# LDA_Board.net
KiCad netlist of a schematic drawn in EAGLE
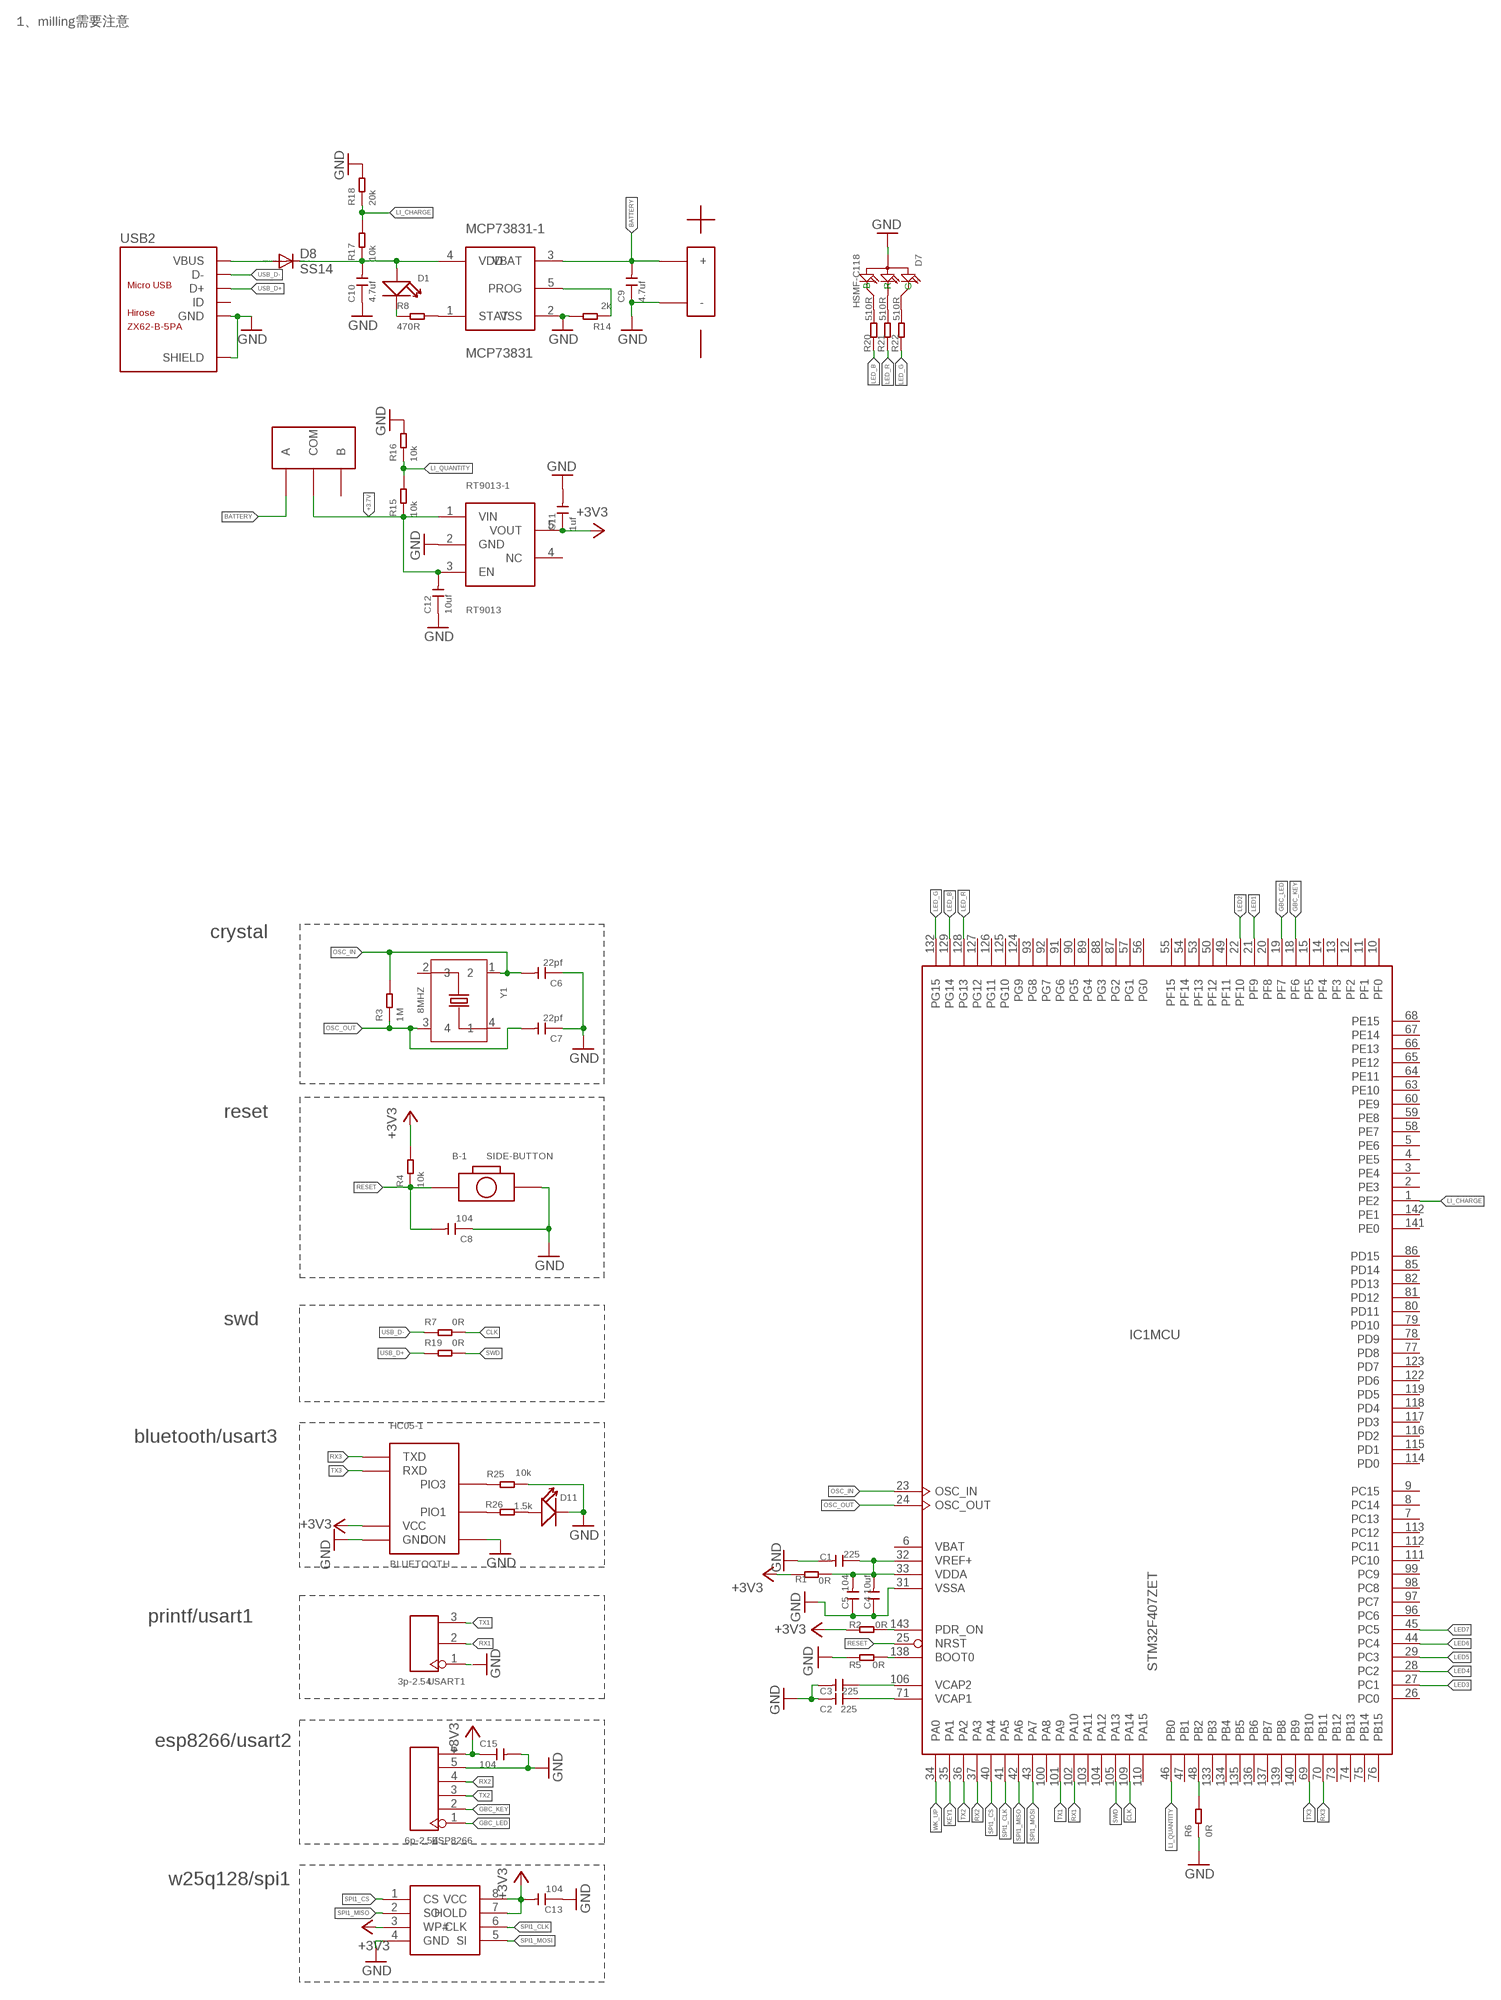
[diagram p0: schematic, sheet 1, part 1 of 2]
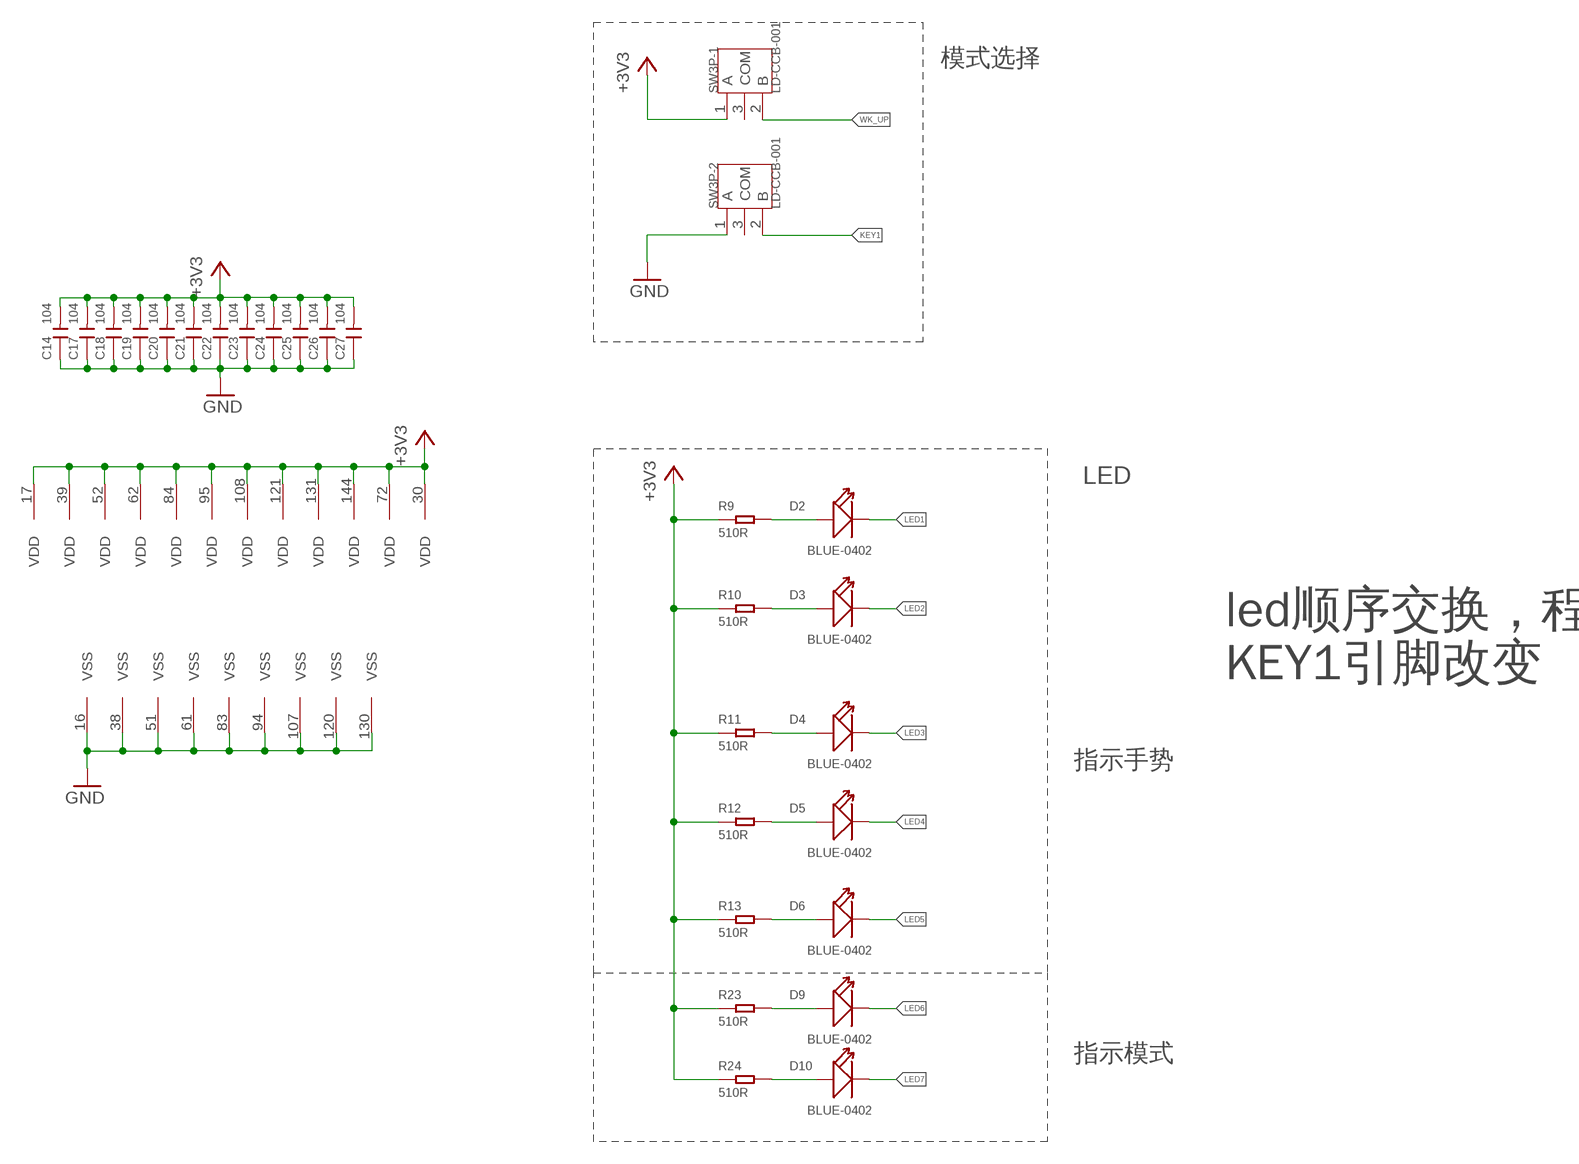
[diagram p1: schematic, sheet 1, part 2 of 2]

(export (version "E")
  (design (tool "Eeschema 10.0.6"))
  (components
    (comp (ref "B-1")
      (value "SIDE-BUTTON")
      (footprint "eagle-import:SIDE-BUTTON")
      (libsource (lib "eagle-import") (part "SIDE-BUTTON"))
    )
    (comp (ref "BATTERY-1")
      (value "BATTERY")
      (footprint "eagle-import:BATTERY")
      (libsource (lib "eagle-import") (part "BATTERY"))
    )
    (comp (ref "C1")
      (value "225")
      (footprint "eagle-import:C0402")
      (fields (field (name "MPN") "GRM1555C1H150JA01D"))
      (libsource (lib "eagle-import") (part "CAP-(0402)"))
    )
    (comp (ref "C2")
      (value "225")
      (footprint "eagle-import:C0402")
      (fields (field (name "MPN") "GRM1555C1H150JA01D"))
      (libsource (lib "eagle-import") (part "CAP-(0402)"))
    )
    (comp (ref "C3")
      (value "225")
      (footprint "eagle-import:C0402")
      (fields (field (name "MPN") "GRM1555C1H150JA01D"))
      (libsource (lib "eagle-import") (part "CAP-(0402)"))
    )
    (comp (ref "C4")
      (value "10uf")
      (footprint "eagle-import:C0402")
      (fields (field (name "MPN") "GRM1555C1H150JA01D"))
      (libsource (lib "eagle-import") (part "CAP-(0402)"))
    )
    (comp (ref "C5")
      (value "104")
      (footprint "eagle-import:C0402")
      (fields (field (name "MPN") "GRM1555C1H150JA01D"))
      (libsource (lib "eagle-import") (part "CAP-(0402)"))
    )
    (comp (ref "C6")
      (value "22pf")
      (footprint "eagle-import:C0402")
      (fields (field (name "MPN") "GRM1555C1H150JA01D"))
      (libsource (lib "eagle-import") (part "CAP-(0402)"))
    )
    (comp (ref "C7")
      (value "22pf")
      (footprint "eagle-import:C0402")
      (fields (field (name "MPN") "GRM1555C1H150JA01D"))
      (libsource (lib "eagle-import") (part "CAP-(0402)"))
    )
    (comp (ref "C8")
      (value "104")
      (footprint "eagle-import:C0402")
      (fields (field (name "MPN") "GRM1555C1H150JA01D"))
      (libsource (lib "eagle-import") (part "CAP-(0402)"))
    )
    (comp (ref "C9")
      (value "4.7uf")
      (footprint "eagle-import:C0402")
      (fields (field (name "MPN") "GRM1555C1H150JA01D"))
      (libsource (lib "eagle-import") (part "CAP-(0402)"))
    )
    (comp (ref "C10")
      (value "4.7uf")
      (footprint "eagle-import:C0402")
      (fields (field (name "MPN") "GRM1555C1H150JA01D"))
      (libsource (lib "eagle-import") (part "CAP-(0402)"))
    )
    (comp (ref "C11")
      (value "1uf")
      (footprint "eagle-import:C0402")
      (fields (field (name "MPN") "GRM1555C1H150JA01D"))
      (libsource (lib "eagle-import") (part "CAP-(0402)"))
    )
    (comp (ref "C12")
      (value "10uf")
      (footprint "eagle-import:C0402")
      (fields (field (name "MPN") "GRM1555C1H150JA01D"))
      (libsource (lib "eagle-import") (part "CAP-(0402)"))
    )
    (comp (ref "C13")
      (value "104")
      (footprint "eagle-import:C0402")
      (fields (field (name "MPN") "GRM1555C1H150JA01D"))
      (libsource (lib "eagle-import") (part "CAP-(0402)"))
    )
    (comp (ref "C14")
      (value "104")
      (footprint "eagle-import:C0402")
      (fields (field (name "MPN") "GRM1555C1H150JA01D"))
      (libsource (lib "eagle-import") (part "CAP-(0402)"))
    )
    (comp (ref "C15")
      (value "104")
      (footprint "eagle-import:C0402")
      (fields (field (name "MPN") "GRM1555C1H150JA01D"))
      (libsource (lib "eagle-import") (part "CAP-(0402)"))
    )
    (comp (ref "C17")
      (value "104")
      (footprint "eagle-import:C0402")
      (fields (field (name "MPN") "GRM1555C1H150JA01D"))
      (libsource (lib "eagle-import") (part "CAP-(0402)"))
    )
    (comp (ref "C18")
      (value "104")
      (footprint "eagle-import:C0402")
      (fields (field (name "MPN") "GRM1555C1H150JA01D"))
      (libsource (lib "eagle-import") (part "CAP-(0402)"))
    )
    (comp (ref "C19")
      (value "104")
      (footprint "eagle-import:C0402")
      (fields (field (name "MPN") "GRM1555C1H150JA01D"))
      (libsource (lib "eagle-import") (part "CAP-(0402)"))
    )
    (comp (ref "C20")
      (value "104")
      (footprint "eagle-import:C0402")
      (fields (field (name "MPN") "GRM1555C1H150JA01D"))
      (libsource (lib "eagle-import") (part "CAP-(0402)"))
    )
    (comp (ref "C21")
      (value "104")
      (footprint "eagle-import:C0402")
      (fields (field (name "MPN") "GRM1555C1H150JA01D"))
      (libsource (lib "eagle-import") (part "CAP-(0402)"))
    )
    (comp (ref "C22")
      (value "104")
      (footprint "eagle-import:C0402")
      (fields (field (name "MPN") "GRM1555C1H150JA01D"))
      (libsource (lib "eagle-import") (part "CAP-(0402)"))
    )
    (comp (ref "C23")
      (value "104")
      (footprint "eagle-import:C0402")
      (fields (field (name "MPN") "GRM1555C1H150JA01D"))
      (libsource (lib "eagle-import") (part "CAP-(0402)"))
    )
    (comp (ref "C24")
      (value "104")
      (footprint "eagle-import:C0402")
      (fields (field (name "MPN") "GRM1555C1H150JA01D"))
      (libsource (lib "eagle-import") (part "CAP-(0402)"))
    )
    (comp (ref "C25")
      (value "104")
      (footprint "eagle-import:C0402")
      (fields (field (name "MPN") "GRM1555C1H150JA01D"))
      (libsource (lib "eagle-import") (part "CAP-(0402)"))
    )
    (comp (ref "C26")
      (value "104")
      (footprint "eagle-import:C0402")
      (fields (field (name "MPN") "GRM1555C1H150JA01D"))
      (libsource (lib "eagle-import") (part "CAP-(0402)"))
    )
    (comp (ref "C27")
      (value "104")
      (footprint "eagle-import:C0402")
      (fields (field (name "MPN") "GRM1555C1H150JA01D"))
      (libsource (lib "eagle-import") (part "CAP-(0402)"))
    )
    (comp (ref "D1")
      (value "BLUE-0402")
      (footprint "eagle-import:LED-0402")
      (fields (field (name "MPN") "BL-HB337A-AV-TRB"))
      (libsource (lib "eagle-import") (part "LED-(0402)"))
    )
    (comp (ref "D2")
      (value "BLUE-0402")
      (footprint "eagle-import:LED-0402")
      (fields (field (name "MPN") "BL-HB337A-AV-TRB"))
      (libsource (lib "eagle-import") (part "LED-(0402)"))
    )
    (comp (ref "D3")
      (value "BLUE-0402")
      (footprint "eagle-import:LED-0402")
      (fields (field (name "MPN") "BL-HB337A-AV-TRB"))
      (libsource (lib "eagle-import") (part "LED-(0402)"))
    )
    (comp (ref "D4")
      (value "BLUE-0402")
      (footprint "eagle-import:LED-0402")
      (fields (field (name "MPN") "BL-HB337A-AV-TRB"))
      (libsource (lib "eagle-import") (part "LED-(0402)"))
    )
    (comp (ref "D5")
      (value "BLUE-0402")
      (footprint "eagle-import:LED-0402")
      (fields (field (name "MPN") "BL-HB337A-AV-TRB"))
      (libsource (lib "eagle-import") (part "LED-(0402)"))
    )
    (comp (ref "D6")
      (value "BLUE-0402")
      (footprint "eagle-import:LED-0402")
      (fields (field (name "MPN") "BL-HB337A-AV-TRB"))
      (libsource (lib "eagle-import") (part "LED-(0402)"))
    )
    (comp (ref "D7")
      (value "HSMF-C118")
      (footprint "eagle-import:LED4-SMD-1210")
      (libsource (lib "eagle-import") (part "SMD-LED-RGB(4P-1210)"))
    )
    (comp (ref "D8")
      (value "SS14")
      (footprint "eagle-import:SMA")
      (libsource (lib "eagle-import") (part "SS14"))
    )
    (comp (ref "D9")
      (value "BLUE-0402")
      (footprint "eagle-import:LED-0402")
      (fields (field (name "MPN") "BL-HB337A-AV-TRB"))
      (libsource (lib "eagle-import") (part "LED-(0402)"))
    )
    (comp (ref "D10")
      (value "BLUE-0402")
      (footprint "eagle-import:LED-0402")
      (fields (field (name "MPN") "BL-HB337A-AV-TRB"))
      (libsource (lib "eagle-import") (part "LED-(0402)"))
    )
    (comp (ref "D11")
      (value "BLUE-0402")
      (footprint "eagle-import:LED-0402")
      (fields (field (name "MPN") "BL-HB337A-AV-TRB"))
      (libsource (lib "eagle-import") (part "LED-(0402)"))
    )
    (comp (ref "ESP8266")
      (value "6p-2.54")
      (footprint "eagle-import:H6-2.54")
      (fields (field (name "MPN") "F185-1106A1BSYC1"))
      (libsource (lib "eagle-import") (part "DIP-BLACK-FEMALE-HEADER-VERT(6P-2.54)"))
    )
    (comp (ref "HC05-1")
      (value "BLUETOOTH")
      (footprint "eagle-import:BLUETOOTH")
      (libsource (lib "eagle-import") (part "BLUETOOTH"))
    )
    (comp (ref "IC1")
      (value "STM32F407ZET")
      (footprint "eagle-import:LQFP144")
      (libsource (lib "eagle-import") (part "STM32F407ZTE"))
    )
    (comp (ref "MCP73831-1")
      (value "MCP73831")
      (footprint "eagle-import:SOT23-5")
      (libsource (lib "eagle-import") (part "MCP73831"))
    )
    (comp (ref "R1")
      (value "0R")
      (footprint "eagle-import:R0402")
      (fields (field (name "MPN") "RC0402JR-070RL"))
      (libsource (lib "eagle-import") (part "RES-(0402)"))
    )
    (comp (ref "R2")
      (value "0R")
      (footprint "eagle-import:R0402")
      (fields (field (name "MPN") "RC0402JR-070RL"))
      (libsource (lib "eagle-import") (part "RES-(0402)"))
    )
    (comp (ref "R3")
      (value "1M")
      (footprint "eagle-import:R0402")
      (fields (field (name "MPN") "RC0402JR-070RL"))
      (libsource (lib "eagle-import") (part "RES-(0402)"))
    )
    (comp (ref "R4")
      (value "10k")
      (footprint "eagle-import:R0402")
      (fields (field (name "MPN") "RC0402JR-070RL"))
      (libsource (lib "eagle-import") (part "RES-(0402)"))
    )
    (comp (ref "R5")
      (value "0R")
      (footprint "eagle-import:R0402")
      (fields (field (name "MPN") "RC0402JR-070RL"))
      (libsource (lib "eagle-import") (part "RES-(0402)"))
    )
    (comp (ref "R6")
      (value "0R")
      (footprint "eagle-import:R0402")
      (fields (field (name "MPN") "RC0402JR-070RL"))
      (libsource (lib "eagle-import") (part "RES-(0402)"))
    )
    (comp (ref "R7")
      (value "0R")
      (footprint "eagle-import:R0402")
      (fields (field (name "MPN") "RC0402JR-070RL"))
      (libsource (lib "eagle-import") (part "RES-(0402)"))
    )
    (comp (ref "R8")
      (value "470R")
      (footprint "eagle-import:R0402")
      (fields (field (name "MPN") "RC0402JR-070RL"))
      (libsource (lib "eagle-import") (part "RES-(0402)"))
    )
    (comp (ref "R9")
      (value "510R")
      (footprint "eagle-import:R0402")
      (fields (field (name "MPN") "RC0402JR-070RL"))
      (libsource (lib "eagle-import") (part "RES-(0402)"))
    )
    (comp (ref "R10")
      (value "510R")
      (footprint "eagle-import:R0402")
      (fields (field (name "MPN") "RC0402JR-070RL"))
      (libsource (lib "eagle-import") (part "RES-(0402)"))
    )
    (comp (ref "R11")
      (value "510R")
      (footprint "eagle-import:R0402")
      (fields (field (name "MPN") "RC0402JR-070RL"))
      (libsource (lib "eagle-import") (part "RES-(0402)"))
    )
    (comp (ref "R12")
      (value "510R")
      (footprint "eagle-import:R0402")
      (fields (field (name "MPN") "RC0402JR-070RL"))
      (libsource (lib "eagle-import") (part "RES-(0402)"))
    )
    (comp (ref "R13")
      (value "510R")
      (footprint "eagle-import:R0402")
      (fields (field (name "MPN") "RC0402JR-070RL"))
      (libsource (lib "eagle-import") (part "RES-(0402)"))
    )
    (comp (ref "R14")
      (value "2k")
      (footprint "eagle-import:R0402")
      (fields (field (name "MPN") "RC0402JR-070RL"))
      (libsource (lib "eagle-import") (part "RES-(0402)"))
    )
    (comp (ref "R15")
      (value "10k")
      (footprint "eagle-import:R0402")
      (fields (field (name "MPN") "RC0402JR-070RL"))
      (libsource (lib "eagle-import") (part "RES-(0402)"))
    )
    (comp (ref "R16")
      (value "10k")
      (footprint "eagle-import:R0402")
      (fields (field (name "MPN") "RC0402JR-070RL"))
      (libsource (lib "eagle-import") (part "RES-(0402)"))
    )
    (comp (ref "R17")
      (value "10k")
      (footprint "eagle-import:R0402")
      (fields (field (name "MPN") "RC0402JR-070RL"))
      (libsource (lib "eagle-import") (part "RES-(0402)"))
    )
    (comp (ref "R18")
      (value "20k")
      (footprint "eagle-import:R0402")
      (fields (field (name "MPN") "RC0402JR-070RL"))
      (libsource (lib "eagle-import") (part "RES-(0402)"))
    )
    (comp (ref "R19")
      (value "0R")
      (footprint "eagle-import:R0402")
      (fields (field (name "MPN") "RC0402JR-070RL"))
      (libsource (lib "eagle-import") (part "RES-(0402)"))
    )
    (comp (ref "R20")
      (value "510R")
      (footprint "eagle-import:R0402")
      (fields (field (name "MPN") "RC0402JR-070RL"))
      (libsource (lib "eagle-import") (part "RES-(0402)"))
    )
    (comp (ref "R21")
      (value "510R")
      (footprint "eagle-import:R0402")
      (fields (field (name "MPN") "RC0402JR-070RL"))
      (libsource (lib "eagle-import") (part "RES-(0402)"))
    )
    (comp (ref "R22")
      (value "510R")
      (footprint "eagle-import:R0402")
      (fields (field (name "MPN") "RC0402JR-070RL"))
      (libsource (lib "eagle-import") (part "RES-(0402)"))
    )
    (comp (ref "R23")
      (value "510R")
      (footprint "eagle-import:R0402")
      (fields (field (name "MPN") "RC0402JR-070RL"))
      (libsource (lib "eagle-import") (part "RES-(0402)"))
    )
    (comp (ref "R24")
      (value "510R")
      (footprint "eagle-import:R0402")
      (fields (field (name "MPN") "RC0402JR-070RL"))
      (libsource (lib "eagle-import") (part "RES-(0402)"))
    )
    (comp (ref "R25")
      (value "10k")
      (footprint "eagle-import:R0402")
      (fields (field (name "MPN") "RC0402JR-070RL"))
      (libsource (lib "eagle-import") (part "RES-(0402)"))
    )
    (comp (ref "R26")
      (value "1.5k")
      (footprint "eagle-import:R0402")
      (fields (field (name "MPN") "RC0402JR-070RL"))
      (libsource (lib "eagle-import") (part "RES-(0402)"))
    )
    (comp (ref "RT9013-1")
      (value "RT9013")
      (footprint "eagle-import:SOT23-5")
      (libsource (lib "eagle-import") (part "RT9013"))
    )
    (comp (ref "SW-1")
      (value "SWITCH-3P")
      (footprint "eagle-import:SWITCH-3P")
      (libsource (lib "eagle-import") (part "SWITCH-3P"))
    )
    (comp (ref "SW3P-1")
      (value "LD-CCB-001")
      (footprint "eagle-import:SW3-2.54-9.0X3.5X3.5+2.0MM")
      (libsource (lib "eagle-import") (part "SWITCH(3P)"))
    )
    (comp (ref "SW3P-2")
      (value "LD-CCB-001")
      (footprint "eagle-import:SW3-2.54-9.0X3.5X3.5+2.0MM")
      (libsource (lib "eagle-import") (part "SWITCH(3P)"))
    )
    (comp (ref "USART1")
      (value "3p-2.54")
      (footprint "eagle-import:H3-2.54")
      (fields (field (name "MPN") "F185-1103A0BSYA1"))
      (libsource (lib "eagle-import") (part "DIP-BLACK-FEMALE-HEADER-VERT(3P-2.54)"))
    )
    (comp (ref "USB2")
      (value "ZX62-B-5PA")
      (footprint "eagle-import:MICRO-USB5+6P-SMD-0.65-AB")
      (libsource (lib "eagle-import") (part "MICRO-USB-SMD(ZX62-B-5PA)"))
    )
    (comp (ref "W25Q128")
      (value "W25Q128")
      (footprint "eagle-import:SOP08")
      (libsource (lib "eagle-import") (part "W25Q128"))
    )
    (comp (ref "Y1")
      (value "8MHZ")
      (footprint "eagle-import:X4-SMD-3.2X2.5X0.7MM")
      (fields (field (name "MPN") "7M-27.120MAAJ-T"))
      (libsource (lib "eagle-import") (part "SMD-CRYSTAL-27.12MHZ-18PF-30PPM-60R(4P-3.2X2.5MM)"))
    )
  )
  (nets
    (net (code "1") (name "+3.7V") (class "Default")
      (node (ref "C12") (pin "2") (pinfunction "2_2") (pintype "passive"))
      (node (ref "R15") (pin "1") (pinfunction "1_1") (pintype "passive"))
      (node (ref "RT9013-1") (pin "1") (pinfunction "VIN_1") (pintype "bidirectional"))
      (node (ref "RT9013-1") (pin "3") (pinfunction "EN_3") (pintype "bidirectional"))
      (node (ref "SW-1") (pin "P$2") (pinfunction "COM_P$2") (pintype "bidirectional"))
    )
    (net (code "2") (name "+3V3") (class "Default")
      (node (ref "C11") (pin "1") (pinfunction "1_1") (pintype "passive"))
      (node (ref "C13") (pin "2") (pinfunction "2_2") (pintype "passive"))
      (node (ref "C14") (pin "2") (pinfunction "2_2") (pintype "passive"))
      (node (ref "C15") (pin "1") (pinfunction "1_1") (pintype "passive"))
      (node (ref "C17") (pin "2") (pinfunction "2_2") (pintype "passive"))
      (node (ref "C18") (pin "2") (pinfunction "2_2") (pintype "passive"))
      (node (ref "C19") (pin "2") (pinfunction "2_2") (pintype "passive"))
      (node (ref "C20") (pin "2") (pinfunction "2_2") (pintype "passive"))
      (node (ref "C21") (pin "2") (pinfunction "2_2") (pintype "passive"))
      (node (ref "C22") (pin "2") (pinfunction "2_2") (pintype "passive"))
      (node (ref "C23") (pin "2") (pinfunction "2_2") (pintype "passive"))
      (node (ref "C24") (pin "2") (pinfunction "2_2") (pintype "passive"))
      (node (ref "C25") (pin "2") (pinfunction "2_2") (pintype "passive"))
      (node (ref "C26") (pin "2") (pinfunction "2_2") (pintype "passive"))
      (node (ref "C27") (pin "2") (pinfunction "2_2") (pintype "passive"))
      (node (ref "ESP8266") (pin "6") (pinfunction "6_6") (pintype "bidirectional"))
      (node (ref "HC05-1") (pin "P$12") (pinfunction "VCC_P$12") (pintype "bidirectional"))
      (node (ref "IC1") (pin "108") (pinfunction "VDD_108") (pintype "power_in"))
      (node (ref "IC1") (pin "121") (pinfunction "VDD_121") (pintype "power_in"))
      (node (ref "IC1") (pin "131") (pinfunction "VDD_131") (pintype "power_in"))
      (node (ref "IC1") (pin "144") (pinfunction "VDD_144") (pintype "power_in"))
      (node (ref "IC1") (pin "17") (pinfunction "VDD_17") (pintype "power_in"))
      (node (ref "IC1") (pin "30") (pinfunction "VDD_30") (pintype "power_in"))
      (node (ref "IC1") (pin "39") (pinfunction "VDD_39") (pintype "power_in"))
      (node (ref "IC1") (pin "52") (pinfunction "VDD_52") (pintype "power_in"))
      (node (ref "IC1") (pin "62") (pinfunction "VDD_62") (pintype "power_in"))
      (node (ref "IC1") (pin "72") (pinfunction "VDD_72") (pintype "power_in"))
      (node (ref "IC1") (pin "84") (pinfunction "VDD_84") (pintype "power_in"))
      (node (ref "IC1") (pin "95") (pinfunction "VDD_95") (pintype "power_in"))
      (node (ref "R1") (pin "1") (pinfunction "1_1") (pintype "passive"))
      (node (ref "R10") (pin "1") (pinfunction "1_1") (pintype "passive"))
      (node (ref "R11") (pin "1") (pinfunction "1_1") (pintype "passive"))
      (node (ref "R12") (pin "1") (pinfunction "1_1") (pintype "passive"))
      (node (ref "R13") (pin "1") (pinfunction "1_1") (pintype "passive"))
      (node (ref "R2") (pin "1") (pinfunction "1_1") (pintype "passive"))
      (node (ref "R23") (pin "1") (pinfunction "1_1") (pintype "passive"))
      (node (ref "R24") (pin "1") (pinfunction "1_1") (pintype "passive"))
      (node (ref "R4") (pin "2") (pinfunction "2_2") (pintype "passive"))
      (node (ref "R9") (pin "1") (pinfunction "1_1") (pintype "passive"))
      (node (ref "RT9013-1") (pin "5") (pinfunction "VOUT_5") (pintype "bidirectional"))
      (node (ref "SW3P-1") (pin "1") (pinfunction "A_1") (pintype "bidirectional"))
      (node (ref "W25Q128") (pin "3") (pinfunction "WP#_3") (pintype "bidirectional"))
      (node (ref "W25Q128") (pin "7") (pinfunction "HOLD_7") (pintype "bidirectional"))
      (node (ref "W25Q128") (pin "8") (pinfunction "VCC_8") (pintype "bidirectional"))
    )
    (net (code "3") (name "/VBAT") (class "Default")
      (node (ref "IC1") (pin "6") (pinfunction "VBAT_6") (pintype "power_in"))
    )
    (net (code "4") (name "BATTERY") (class "Default")
      (node (ref "BATTERY-1") (pin "P$1") (pinfunction "+_P$1") (pintype "bidirectional"))
      (node (ref "C9") (pin "2") (pinfunction "2_2") (pintype "passive"))
      (node (ref "MCP73831-1") (pin "3") (pinfunction "VBAT_3") (pintype "bidirectional"))
      (node (ref "SW-1") (pin "P$3") (pinfunction "A_P$3") (pintype "bidirectional"))
    )
    (net (code "5") (name "CLK") (class "Default")
      (node (ref "IC1") (pin "109") (pinfunction "PA14_109") (pintype "bidirectional"))
      (node (ref "R7") (pin "2") (pinfunction "2_2") (pintype "passive"))
    )
    (net (code "6") (name "GBC_KEY") (class "Default")
      (node (ref "ESP8266") (pin "2") (pinfunction "2_2") (pintype "bidirectional"))
      (node (ref "IC1") (pin "18") (pinfunction "PF6_18") (pintype "bidirectional"))
    )
    (net (code "7") (name "GBC_LED") (class "Default")
      (node (ref "ESP8266") (pin "1") (pinfunction "1_1") (pintype "bidirectional"))
      (node (ref "IC1") (pin "19") (pinfunction "PF7_19") (pintype "bidirectional"))
    )
    (net (code "8") (name "GND") (class "Default")
      (node (ref "B-1") (pin "P$1") (pinfunction "2_P$1") (pintype "bidirectional"))
      (node (ref "BATTERY-1") (pin "P$2") (pinfunction "-_P$2") (pintype "bidirectional"))
      (node (ref "C1") (pin "2") (pinfunction "2_2") (pintype "passive"))
      (node (ref "C10") (pin "1") (pinfunction "1_1") (pintype "passive"))
      (node (ref "C11") (pin "2") (pinfunction "2_2") (pintype "passive"))
      (node (ref "C12") (pin "1") (pinfunction "1_1") (pintype "passive"))
      (node (ref "C13") (pin "1") (pinfunction "1_1") (pintype "passive"))
      (node (ref "C14") (pin "1") (pinfunction "1_1") (pintype "passive"))
      (node (ref "C15") (pin "2") (pinfunction "2_2") (pintype "passive"))
      (node (ref "C17") (pin "1") (pinfunction "1_1") (pintype "passive"))
      (node (ref "C18") (pin "1") (pinfunction "1_1") (pintype "passive"))
      (node (ref "C19") (pin "1") (pinfunction "1_1") (pintype "passive"))
      (node (ref "C2") (pin "2") (pinfunction "2_2") (pintype "passive"))
      (node (ref "C20") (pin "1") (pinfunction "1_1") (pintype "passive"))
      (node (ref "C21") (pin "1") (pinfunction "1_1") (pintype "passive"))
      (node (ref "C22") (pin "1") (pinfunction "1_1") (pintype "passive"))
      (node (ref "C23") (pin "1") (pinfunction "1_1") (pintype "passive"))
      (node (ref "C24") (pin "1") (pinfunction "1_1") (pintype "passive"))
      (node (ref "C25") (pin "1") (pinfunction "1_1") (pintype "passive"))
      (node (ref "C26") (pin "1") (pinfunction "1_1") (pintype "passive"))
      (node (ref "C27") (pin "1") (pinfunction "1_1") (pintype "passive"))
      (node (ref "C3") (pin "2") (pinfunction "2_2") (pintype "passive"))
      (node (ref "C4") (pin "1") (pinfunction "1_1") (pintype "passive"))
      (node (ref "C5") (pin "1") (pinfunction "1_1") (pintype "passive"))
      (node (ref "C6") (pin "1") (pinfunction "1_1") (pintype "passive"))
      (node (ref "C7") (pin "1") (pinfunction "1_1") (pintype "passive"))
      (node (ref "C8") (pin "1") (pinfunction "1_1") (pintype "passive"))
      (node (ref "C9") (pin "1") (pinfunction "1_1") (pintype "passive"))
      (node (ref "D11") (pin "-") (pinfunction "-_-") (pintype "passive"))
      (node (ref "D7") (pin "1") (pinfunction "+_1") (pintype "bidirectional"))
      (node (ref "ESP8266") (pin "5") (pinfunction "5_5") (pintype "bidirectional"))
      (node (ref "HC05-1") (pin "P$13") (pinfunction "GND_P$13") (pintype "bidirectional"))
      (node (ref "HC05-1") (pin "P$22") (pinfunction "CON_P$22") (pintype "bidirectional"))
      (node (ref "IC1") (pin "107") (pinfunction "VSS_107") (pintype "power_in"))
      (node (ref "IC1") (pin "120") (pinfunction "VSS_120") (pintype "power_in"))
      (node (ref "IC1") (pin "130") (pinfunction "VSS_130") (pintype "power_in"))
      (node (ref "IC1") (pin "16") (pinfunction "VSS_16") (pintype "power_in"))
      (node (ref "IC1") (pin "31") (pinfunction "VSSA_31") (pintype "power_in"))
      (node (ref "IC1") (pin "38") (pinfunction "VSS_38") (pintype "power_in"))
      (node (ref "IC1") (pin "51") (pinfunction "VSS_51") (pintype "power_in"))
      (node (ref "IC1") (pin "61") (pinfunction "VSS_61") (pintype "power_in"))
      (node (ref "IC1") (pin "83") (pinfunction "VSS_83") (pintype "power_in"))
      (node (ref "IC1") (pin "94") (pinfunction "VSS_94") (pintype "power_in"))
      (node (ref "MCP73831-1") (pin "2") (pinfunction "VSS_2") (pintype "bidirectional"))
      (node (ref "R14") (pin "2") (pinfunction "2_2") (pintype "passive"))
      (node (ref "R16") (pin "2") (pinfunction "2_2") (pintype "passive"))
      (node (ref "R18") (pin "2") (pinfunction "2_2") (pintype "passive"))
      (node (ref "R25") (pin "2") (pinfunction "2_2") (pintype "passive"))
      (node (ref "R5") (pin "1") (pinfunction "1_1") (pintype "passive"))
      (node (ref "R6") (pin "1") (pinfunction "1_1") (pintype "passive"))
      (node (ref "RT9013-1") (pin "2") (pinfunction "GND_2") (pintype "bidirectional"))
      (node (ref "SW3P-2") (pin "1") (pinfunction "A_1") (pintype "bidirectional"))
      (node (ref "USART1") (pin "1") (pinfunction "P$1_1") (pintype "bidirectional"))
      (node (ref "USB2") (pin "5") (pinfunction "GND_5") (pintype "power_in"))
      (node (ref "USB2") (pin "P1") (pinfunction "SHIELD_P1") (pintype "power_in"))
      (node (ref "USB2") (pin "P2") (pinfunction "SHIELD_P2") (pintype "power_in"))
      (node (ref "USB2") (pin "P3") (pinfunction "SHIELD_P3") (pintype "power_in"))
      (node (ref "USB2") (pin "P4") (pinfunction "SHIELD_P4") (pintype "power_in"))
      (node (ref "USB2") (pin "P5") (pinfunction "SHIELD_P5") (pintype "power_in"))
      (node (ref "USB2") (pin "P6") (pinfunction "SHIELD_P6") (pintype "power_in"))
      (node (ref "W25Q128") (pin "4") (pinfunction "GND_4") (pintype "bidirectional"))
    )
    (net (code "9") (name "KEY1") (class "Default")
      (node (ref "IC1") (pin "35") (pinfunction "PA1_35") (pintype "bidirectional"))
      (node (ref "SW3P-2") (pin "2") (pinfunction "B_2") (pintype "bidirectional"))
    )
    (net (code "10") (name "LED1") (class "Default")
      (node (ref "D2") (pin "-") (pinfunction "-_-") (pintype "passive"))
      (node (ref "IC1") (pin "21") (pinfunction "PF9_21") (pintype "bidirectional"))
    )
    (net (code "11") (name "LED2") (class "Default")
      (node (ref "D3") (pin "-") (pinfunction "-_-") (pintype "passive"))
      (node (ref "IC1") (pin "22") (pinfunction "PF10_22") (pintype "bidirectional"))
    )
    (net (code "12") (name "LED3") (class "Default")
      (node (ref "D4") (pin "-") (pinfunction "-_-") (pintype "passive"))
      (node (ref "IC1") (pin "27") (pinfunction "PC1_27") (pintype "bidirectional"))
    )
    (net (code "13") (name "LED4") (class "Default")
      (node (ref "D5") (pin "-") (pinfunction "-_-") (pintype "passive"))
      (node (ref "IC1") (pin "28") (pinfunction "PC2_28") (pintype "bidirectional"))
    )
    (net (code "14") (name "LED5") (class "Default")
      (node (ref "D6") (pin "-") (pinfunction "-_-") (pintype "passive"))
      (node (ref "IC1") (pin "29") (pinfunction "PC3_29") (pintype "bidirectional"))
    )
    (net (code "15") (name "LED6") (class "Default")
      (node (ref "D9") (pin "-") (pinfunction "-_-") (pintype "passive"))
      (node (ref "IC1") (pin "44") (pinfunction "PC4_44") (pintype "bidirectional"))
    )
    (net (code "16") (name "LED7") (class "Default")
      (node (ref "D10") (pin "-") (pinfunction "-_-") (pintype "passive"))
      (node (ref "IC1") (pin "45") (pinfunction "PC5_45") (pintype "bidirectional"))
    )
    (net (code "17") (name "LED_B") (class "Default")
      (node (ref "IC1") (pin "129") (pinfunction "PG14_129") (pintype "bidirectional"))
      (node (ref "R20") (pin "1") (pinfunction "1_1") (pintype "passive"))
    )
    (net (code "18") (name "LED_G") (class "Default")
      (node (ref "IC1") (pin "132") (pinfunction "PG15_132") (pintype "bidirectional"))
      (node (ref "R22") (pin "1") (pinfunction "1_1") (pintype "passive"))
    )
    (net (code "19") (name "LED_R") (class "Default")
      (node (ref "IC1") (pin "128") (pinfunction "PG13_128") (pintype "bidirectional"))
      (node (ref "R21") (pin "1") (pinfunction "1_1") (pintype "passive"))
    )
    (net (code "20") (name "LI_CHARGE") (class "Default")
      (node (ref "IC1") (pin "1") (pinfunction "PE2_1") (pintype "bidirectional"))
      (node (ref "R17") (pin "2") (pinfunction "2_2") (pintype "passive"))
      (node (ref "R18") (pin "1") (pinfunction "1_1") (pintype "passive"))
    )
    (net (code "21") (name "LI_QUANTITY") (class "Default")
      (node (ref "IC1") (pin "46") (pinfunction "PB0_46") (pintype "bidirectional"))
      (node (ref "R15") (pin "2") (pinfunction "2_2") (pintype "passive"))
      (node (ref "R16") (pin "1") (pinfunction "1_1") (pintype "passive"))
    )
    (net (code "22") (name "Net-(D1-Pad-)") (class "Default")
      (node (ref "D1") (pin "-") (pinfunction "-_-") (pintype "passive"))
      (node (ref "R8") (pin "1") (pinfunction "1_1") (pintype "passive"))
    )
    (net (code "23") (name "Net-(D2-Pad+)") (class "Default")
      (node (ref "D2") (pin "+") (pinfunction "+_+") (pintype "passive"))
      (node (ref "R9") (pin "2") (pinfunction "2_2") (pintype "passive"))
    )
    (net (code "24") (name "Net-(D3-Pad+)") (class "Default")
      (node (ref "D3") (pin "+") (pinfunction "+_+") (pintype "passive"))
      (node (ref "R10") (pin "2") (pinfunction "2_2") (pintype "passive"))
    )
    (net (code "25") (name "Net-(D4-Pad+)") (class "Default")
      (node (ref "D4") (pin "+") (pinfunction "+_+") (pintype "passive"))
      (node (ref "R11") (pin "2") (pinfunction "2_2") (pintype "passive"))
    )
    (net (code "26") (name "Net-(D5-Pad+)") (class "Default")
      (node (ref "D5") (pin "+") (pinfunction "+_+") (pintype "passive"))
      (node (ref "R12") (pin "2") (pinfunction "2_2") (pintype "passive"))
    )
    (net (code "27") (name "Net-(D6-Pad+)") (class "Default")
      (node (ref "D6") (pin "+") (pinfunction "+_+") (pintype "passive"))
      (node (ref "R13") (pin "2") (pinfunction "2_2") (pintype "passive"))
    )
    (net (code "28") (name "Net-(D7-B)") (class "Default")
      (node (ref "D7") (pin "4") (pinfunction "B_4") (pintype "bidirectional"))
      (node (ref "R20") (pin "2") (pinfunction "2_2") (pintype "passive"))
    )
    (net (code "29") (name "Net-(D7-G)") (class "Default")
      (node (ref "D7") (pin "3") (pinfunction "G_3") (pintype "bidirectional"))
      (node (ref "R22") (pin "2") (pinfunction "2_2") (pintype "passive"))
    )
    (net (code "30") (name "Net-(D7-R)") (class "Default")
      (node (ref "D7") (pin "2") (pinfunction "R_2") (pintype "bidirectional"))
      (node (ref "R21") (pin "2") (pinfunction "2_2") (pintype "passive"))
    )
    (net (code "31") (name "Net-(D9-Pad+)") (class "Default")
      (node (ref "D9") (pin "+") (pinfunction "+_+") (pintype "passive"))
      (node (ref "R23") (pin "2") (pinfunction "2_2") (pintype "passive"))
    )
    (net (code "32") (name "Net-(D10-Pad+)") (class "Default")
      (node (ref "D10") (pin "+") (pinfunction "+_+") (pintype "passive"))
      (node (ref "R24") (pin "2") (pinfunction "2_2") (pintype "passive"))
    )
    (net (code "33") (name "Net-(D11-Pad+)") (class "Default")
      (node (ref "D11") (pin "+") (pinfunction "+_+") (pintype "passive"))
      (node (ref "R26") (pin "2") (pinfunction "2_2") (pintype "passive"))
    )
    (net (code "34") (name "Net-(HC05-1-PIO1)") (class "Default")
      (node (ref "HC05-1") (pin "P$24") (pinfunction "PIO1_P$24") (pintype "bidirectional"))
      (node (ref "R26") (pin "1") (pinfunction "1_1") (pintype "passive"))
    )
    (net (code "35") (name "Net-(HC05-1-PIO3)") (class "Default")
      (node (ref "HC05-1") (pin "P$26") (pinfunction "PIO3_P$26") (pintype "bidirectional"))
      (node (ref "R25") (pin "1") (pinfunction "1_1") (pintype "passive"))
    )
    (net (code "36") (name "Net-(IC1A-BOOT0)") (class "Default")
      (node (ref "IC1") (pin "138") (pinfunction "BOOT0_138") (pintype "input"))
      (node (ref "R5") (pin "2") (pinfunction "2_2") (pintype "passive"))
    )
    (net (code "37") (name "Net-(IC1A-PB2)") (class "Default")
      (node (ref "IC1") (pin "48") (pinfunction "PB2_48") (pintype "bidirectional"))
      (node (ref "R6") (pin "2") (pinfunction "2_2") (pintype "passive"))
    )
    (net (code "38") (name "Net-(IC1A-PDR_ON)") (class "Default")
      (node (ref "IC1") (pin "143") (pinfunction "PDR_ON_143") (pintype "input"))
      (node (ref "R2") (pin "2") (pinfunction "2_2") (pintype "passive"))
    )
    (net (code "39") (name "Net-(IC1A-VCAP1)") (class "Default")
      (node (ref "C2") (pin "1") (pinfunction "1_1") (pintype "passive"))
      (node (ref "IC1") (pin "71") (pinfunction "VCAP1_71") (pintype "power_in"))
    )
    (net (code "40") (name "Net-(IC1A-VCAP2)") (class "Default")
      (node (ref "C3") (pin "1") (pinfunction "1_1") (pintype "passive"))
      (node (ref "IC1") (pin "106") (pinfunction "VCAP2_106") (pintype "power_in"))
    )
    (net (code "41") (name "Net-(IC1A-VDDA)") (class "Default")
      (node (ref "C1") (pin "1") (pinfunction "1_1") (pintype "passive"))
      (node (ref "C4") (pin "2") (pinfunction "2_2") (pintype "passive"))
      (node (ref "C5") (pin "2") (pinfunction "2_2") (pintype "passive"))
      (node (ref "IC1") (pin "32") (pinfunction "VREF+_32") (pintype "power_in"))
      (node (ref "IC1") (pin "33") (pinfunction "VDDA_33") (pintype "power_in"))
      (node (ref "R1") (pin "2") (pinfunction "2_2") (pintype "passive"))
    )
    (net (code "42") (name "Net-(MCP73831-1-PROG)") (class "Default")
      (node (ref "MCP73831-1") (pin "5") (pinfunction "PROG_5") (pintype "bidirectional"))
      (node (ref "R14") (pin "1") (pinfunction "1_1") (pintype "passive"))
    )
    (net (code "43") (name "Net-(MCP73831-1-STAT)") (class "Default")
      (node (ref "MCP73831-1") (pin "1") (pinfunction "STAT_1") (pintype "bidirectional"))
      (node (ref "R8") (pin "2") (pinfunction "2_2") (pintype "passive"))
    )
    (net (code "44") (name "Net-(MCP73831-1-VDD)") (class "Default")
      (node (ref "C10") (pin "2") (pinfunction "2_2") (pintype "passive"))
      (node (ref "D1") (pin "+") (pinfunction "+_+") (pintype "passive"))
      (node (ref "D8") (pin "C") (pinfunction "C_C") (pintype "passive"))
      (node (ref "MCP73831-1") (pin "4") (pinfunction "VDD_4") (pintype "bidirectional"))
      (node (ref "R17") (pin "1") (pinfunction "1_1") (pintype "passive"))
    )
    (net (code "45") (name "Net-(USB2-VBUS)") (class "Default")
      (node (ref "D8") (pin "A") (pinfunction "A_A") (pintype "passive"))
      (node (ref "USB2") (pin "1") (pinfunction "VBUS_1") (pintype "power_in"))
    )
    (net (code "46") (name "OSC_IN") (class "Default")
      (node (ref "C6") (pin "2") (pinfunction "2_2") (pintype "passive"))
      (node (ref "IC1") (pin "23") (pinfunction "OSC_IN_23") (pintype "bidirectional"))
      (node (ref "R3") (pin "2") (pinfunction "2_2") (pintype "passive"))
      (node (ref "Y1") (pin "1") (pinfunction "2_1") (pintype "bidirectional"))
    )
    (net (code "47") (name "OSC_OUT") (class "Default")
      (node (ref "C7") (pin "2") (pinfunction "2_2") (pintype "passive"))
      (node (ref "IC1") (pin "24") (pinfunction "OSC_OUT_24") (pintype "bidirectional"))
      (node (ref "R3") (pin "1") (pinfunction "1_1") (pintype "passive"))
      (node (ref "Y1") (pin "3") (pinfunction "4_3") (pintype "bidirectional"))
    )
    (net (code "48") (name "RESET") (class "Default")
      (node (ref "B-1") (pin "P$2") (pinfunction "1_P$2") (pintype "bidirectional"))
      (node (ref "C8") (pin "2") (pinfunction "2_2") (pintype "passive"))
      (node (ref "IC1") (pin "25") (pinfunction "NRST_25") (pintype "bidirectional"))
      (node (ref "R4") (pin "1") (pinfunction "1_1") (pintype "passive"))
    )
    (net (code "49") (name "RX1") (class "Default")
      (node (ref "IC1") (pin "102") (pinfunction "PA10_102") (pintype "bidirectional"))
      (node (ref "USART1") (pin "2") (pinfunction "P$2_2") (pintype "bidirectional"))
    )
    (net (code "50") (name "RX2") (class "Default")
      (node (ref "ESP8266") (pin "4") (pinfunction "4_4") (pintype "bidirectional"))
      (node (ref "IC1") (pin "37") (pinfunction "PA3_37") (pintype "bidirectional"))
    )
    (net (code "51") (name "RX3") (class "Default")
      (node (ref "HC05-1") (pin "P$1") (pinfunction "TXD_P$1") (pintype "bidirectional"))
      (node (ref "IC1") (pin "70") (pinfunction "PB11_70") (pintype "bidirectional"))
    )
    (net (code "52") (name "SPI1_CLK") (class "Default")
      (node (ref "IC1") (pin "41") (pinfunction "PA5_41") (pintype "bidirectional"))
      (node (ref "W25Q128") (pin "6") (pinfunction "CLK_6") (pintype "bidirectional"))
    )
    (net (code "53") (name "SPI1_CS") (class "Default")
      (node (ref "IC1") (pin "40") (pinfunction "PA4_40") (pintype "bidirectional"))
      (node (ref "W25Q128") (pin "1") (pinfunction "CS_1") (pintype "bidirectional"))
    )
    (net (code "54") (name "SPI1_MISO") (class "Default")
      (node (ref "IC1") (pin "42") (pinfunction "PA6_42") (pintype "bidirectional"))
      (node (ref "W25Q128") (pin "2") (pinfunction "SO_2") (pintype "bidirectional"))
    )
    (net (code "55") (name "SPI1_MOSI") (class "Default")
      (node (ref "IC1") (pin "43") (pinfunction "PA7_43") (pintype "bidirectional"))
      (node (ref "W25Q128") (pin "5") (pinfunction "SI_5") (pintype "bidirectional"))
    )
    (net (code "56") (name "SWD") (class "Default")
      (node (ref "IC1") (pin "105") (pinfunction "PA13_105") (pintype "bidirectional"))
      (node (ref "R19") (pin "2") (pinfunction "2_2") (pintype "passive"))
    )
    (net (code "57") (name "TX1") (class "Default")
      (node (ref "IC1") (pin "101") (pinfunction "PA9_101") (pintype "bidirectional"))
      (node (ref "USART1") (pin "3") (pinfunction "P$3_3") (pintype "bidirectional"))
    )
    (net (code "58") (name "TX2") (class "Default")
      (node (ref "ESP8266") (pin "3") (pinfunction "3_3") (pintype "bidirectional"))
      (node (ref "IC1") (pin "36") (pinfunction "PA2_36") (pintype "bidirectional"))
    )
    (net (code "59") (name "TX3") (class "Default")
      (node (ref "HC05-1") (pin "P$2") (pinfunction "RXD_P$2") (pintype "bidirectional"))
      (node (ref "IC1") (pin "69") (pinfunction "PB10_69") (pintype "bidirectional"))
    )
    (net (code "60") (name "USB_D+") (class "Default")
      (node (ref "R19") (pin "1") (pinfunction "1_1") (pintype "passive"))
      (node (ref "USB2") (pin "3") (pinfunction "D+_3") (pintype "bidirectional"))
    )
    (net (code "61") (name "USB_D-") (class "Default")
      (node (ref "R7") (pin "1") (pinfunction "1_1") (pintype "passive"))
      (node (ref "USB2") (pin "2") (pinfunction "D-_2") (pintype "bidirectional"))
    )
    (net (code "62") (name "WK_UP") (class "Default")
      (node (ref "IC1") (pin "34") (pinfunction "PA0_34") (pintype "bidirectional"))
      (node (ref "SW3P-1") (pin "2") (pinfunction "B_2") (pintype "bidirectional"))
    )
    (net (code "63") (name "unconnected-(IC1A-PA8-Pad100)") (class "Default")
      (node (ref "IC1") (pin "100") (pinfunction "PA8_100") (pintype "bidirectional"))
    )
    (net (code "64") (name "unconnected-(IC1A-PA11-Pad103)") (class "Default")
      (node (ref "IC1") (pin "103") (pinfunction "PA11_103") (pintype "bidirectional"))
    )
    (net (code "65") (name "unconnected-(IC1A-PA12-Pad104)") (class "Default")
      (node (ref "IC1") (pin "104") (pinfunction "PA12_104") (pintype "bidirectional"))
    )
    (net (code "66") (name "unconnected-(IC1A-PA15-Pad110)") (class "Default")
      (node (ref "IC1") (pin "110") (pinfunction "PA15_110") (pintype "bidirectional"))
    )
    (net (code "67") (name "unconnected-(IC1A-PB1-Pad47)") (class "Default")
      (node (ref "IC1") (pin "47") (pinfunction "PB1_47") (pintype "bidirectional"))
    )
    (net (code "68") (name "unconnected-(IC1A-PB3-Pad133)") (class "Default")
      (node (ref "IC1") (pin "133") (pinfunction "PB3_133") (pintype "bidirectional"))
    )
    (net (code "69") (name "unconnected-(IC1A-PB4-Pad134)") (class "Default")
      (node (ref "IC1") (pin "134") (pinfunction "PB4_134") (pintype "bidirectional"))
    )
    (net (code "70") (name "unconnected-(IC1A-PB5-Pad135)") (class "Default")
      (node (ref "IC1") (pin "135") (pinfunction "PB5_135") (pintype "bidirectional"))
    )
    (net (code "71") (name "unconnected-(IC1A-PB6-Pad136)") (class "Default")
      (node (ref "IC1") (pin "136") (pinfunction "PB6_136") (pintype "bidirectional"))
    )
    (net (code "72") (name "unconnected-(IC1A-PB7-Pad137)") (class "Default")
      (node (ref "IC1") (pin "137") (pinfunction "PB7_137") (pintype "bidirectional"))
    )
    (net (code "73") (name "unconnected-(IC1A-PB8-Pad139)") (class "Default")
      (node (ref "IC1") (pin "139") (pinfunction "PB8_139") (pintype "bidirectional"))
    )
    (net (code "74") (name "unconnected-(IC1A-PB9-Pad140)") (class "Default")
      (node (ref "IC1") (pin "140") (pinfunction "PB9_140") (pintype "bidirectional"))
    )
    (net (code "75") (name "unconnected-(IC1A-PB12-Pad73)") (class "Default")
      (node (ref "IC1") (pin "73") (pinfunction "PB12_73") (pintype "bidirectional"))
    )
    (net (code "76") (name "unconnected-(IC1A-PB13-Pad74)") (class "Default")
      (node (ref "IC1") (pin "74") (pinfunction "PB13_74") (pintype "bidirectional"))
    )
    (net (code "77") (name "unconnected-(IC1A-PB14-Pad75)") (class "Default")
      (node (ref "IC1") (pin "75") (pinfunction "PB14_75") (pintype "bidirectional"))
    )
    (net (code "78") (name "unconnected-(IC1A-PB15-Pad76)") (class "Default")
      (node (ref "IC1") (pin "76") (pinfunction "PB15_76") (pintype "bidirectional"))
    )
    (net (code "79") (name "unconnected-(IC1A-PC0-Pad26)") (class "Default")
      (node (ref "IC1") (pin "26") (pinfunction "PC0_26") (pintype "bidirectional"))
    )
    (net (code "80") (name "unconnected-(IC1A-PC6-Pad96)") (class "Default")
      (node (ref "IC1") (pin "96") (pinfunction "PC6_96") (pintype "bidirectional"))
    )
    (net (code "81") (name "unconnected-(IC1A-PC7-Pad97)") (class "Default")
      (node (ref "IC1") (pin "97") (pinfunction "PC7_97") (pintype "bidirectional"))
    )
    (net (code "82") (name "unconnected-(IC1A-PC8-Pad98)") (class "Default")
      (node (ref "IC1") (pin "98") (pinfunction "PC8_98") (pintype "bidirectional"))
    )
    (net (code "83") (name "unconnected-(IC1A-PC9-Pad99)") (class "Default")
      (node (ref "IC1") (pin "99") (pinfunction "PC9_99") (pintype "bidirectional"))
    )
    (net (code "84") (name "unconnected-(IC1A-PC10-Pad111)") (class "Default")
      (node (ref "IC1") (pin "111") (pinfunction "PC10_111") (pintype "bidirectional"))
    )
    (net (code "85") (name "unconnected-(IC1A-PC11-Pad112)") (class "Default")
      (node (ref "IC1") (pin "112") (pinfunction "PC11_112") (pintype "bidirectional"))
    )
    (net (code "86") (name "unconnected-(IC1A-PC12-Pad113)") (class "Default")
      (node (ref "IC1") (pin "113") (pinfunction "PC12_113") (pintype "bidirectional"))
    )
    (net (code "87") (name "unconnected-(IC1A-PC13-Pad7)") (class "Default")
      (node (ref "IC1") (pin "7") (pinfunction "PC13_7") (pintype "bidirectional"))
    )
    (net (code "88") (name "unconnected-(IC1A-PC14-Pad8)") (class "Default")
      (node (ref "IC1") (pin "8") (pinfunction "PC14_8") (pintype "bidirectional"))
    )
    (net (code "89") (name "unconnected-(IC1A-PC15-Pad9)") (class "Default")
      (node (ref "IC1") (pin "9") (pinfunction "PC15_9") (pintype "bidirectional"))
    )
    (net (code "90") (name "unconnected-(IC1A-PD0-Pad114)") (class "Default")
      (node (ref "IC1") (pin "114") (pinfunction "PD0_114") (pintype "bidirectional"))
    )
    (net (code "91") (name "unconnected-(IC1A-PD1-Pad115)") (class "Default")
      (node (ref "IC1") (pin "115") (pinfunction "PD1_115") (pintype "bidirectional"))
    )
    (net (code "92") (name "unconnected-(IC1A-PD2-Pad116)") (class "Default")
      (node (ref "IC1") (pin "116") (pinfunction "PD2_116") (pintype "bidirectional"))
    )
    (net (code "93") (name "unconnected-(IC1A-PD3-Pad117)") (class "Default")
      (node (ref "IC1") (pin "117") (pinfunction "PD3_117") (pintype "bidirectional"))
    )
    (net (code "94") (name "unconnected-(IC1A-PD4-Pad118)") (class "Default")
      (node (ref "IC1") (pin "118") (pinfunction "PD4_118") (pintype "bidirectional"))
    )
    (net (code "95") (name "unconnected-(IC1A-PD5-Pad119)") (class "Default")
      (node (ref "IC1") (pin "119") (pinfunction "PD5_119") (pintype "bidirectional"))
    )
    (net (code "96") (name "unconnected-(IC1A-PD6-Pad122)") (class "Default")
      (node (ref "IC1") (pin "122") (pinfunction "PD6_122") (pintype "bidirectional"))
    )
    (net (code "97") (name "unconnected-(IC1A-PD7-Pad123)") (class "Default")
      (node (ref "IC1") (pin "123") (pinfunction "PD7_123") (pintype "bidirectional"))
    )
    (net (code "98") (name "unconnected-(IC1A-PD8-Pad77)") (class "Default")
      (node (ref "IC1") (pin "77") (pinfunction "PD8_77") (pintype "bidirectional"))
    )
    (net (code "99") (name "unconnected-(IC1A-PD9-Pad78)") (class "Default")
      (node (ref "IC1") (pin "78") (pinfunction "PD9_78") (pintype "bidirectional"))
    )
    (net (code "100") (name "unconnected-(IC1A-PD10-Pad79)") (class "Default")
      (node (ref "IC1") (pin "79") (pinfunction "PD10_79") (pintype "bidirectional"))
    )
    (net (code "101") (name "unconnected-(IC1A-PD11-Pad80)") (class "Default")
      (node (ref "IC1") (pin "80") (pinfunction "PD11_80") (pintype "bidirectional"))
    )
    (net (code "102") (name "unconnected-(IC1A-PD12-Pad81)") (class "Default")
      (node (ref "IC1") (pin "81") (pinfunction "PD12_81") (pintype "bidirectional"))
    )
    (net (code "103") (name "unconnected-(IC1A-PD13-Pad82)") (class "Default")
      (node (ref "IC1") (pin "82") (pinfunction "PD13_82") (pintype "bidirectional"))
    )
    (net (code "104") (name "unconnected-(IC1A-PD14-Pad85)") (class "Default")
      (node (ref "IC1") (pin "85") (pinfunction "PD14_85") (pintype "bidirectional"))
    )
    (net (code "105") (name "unconnected-(IC1A-PD15-Pad86)") (class "Default")
      (node (ref "IC1") (pin "86") (pinfunction "PD15_86") (pintype "bidirectional"))
    )
    (net (code "106") (name "unconnected-(IC1A-PE0-Pad141)") (class "Default")
      (node (ref "IC1") (pin "141") (pinfunction "PE0_141") (pintype "bidirectional"))
    )
    (net (code "107") (name "unconnected-(IC1A-PE1-Pad142)") (class "Default")
      (node (ref "IC1") (pin "142") (pinfunction "PE1_142") (pintype "bidirectional"))
    )
    (net (code "108") (name "unconnected-(IC1A-PE3-Pad2)") (class "Default")
      (node (ref "IC1") (pin "2") (pinfunction "PE3_2") (pintype "bidirectional"))
    )
    (net (code "109") (name "unconnected-(IC1A-PE4-Pad3)") (class "Default")
      (node (ref "IC1") (pin "3") (pinfunction "PE4_3") (pintype "bidirectional"))
    )
    (net (code "110") (name "unconnected-(IC1A-PE5-Pad4)") (class "Default")
      (node (ref "IC1") (pin "4") (pinfunction "PE5_4") (pintype "bidirectional"))
    )
    (net (code "111") (name "unconnected-(IC1A-PE6-Pad5)") (class "Default")
      (node (ref "IC1") (pin "5") (pinfunction "PE6_5") (pintype "bidirectional"))
    )
    (net (code "112") (name "unconnected-(IC1A-PE7-Pad58)") (class "Default")
      (node (ref "IC1") (pin "58") (pinfunction "PE7_58") (pintype "bidirectional"))
    )
    (net (code "113") (name "unconnected-(IC1A-PE8-Pad59)") (class "Default")
      (node (ref "IC1") (pin "59") (pinfunction "PE8_59") (pintype "bidirectional"))
    )
    (net (code "114") (name "unconnected-(IC1A-PE9-Pad60)") (class "Default")
      (node (ref "IC1") (pin "60") (pinfunction "PE9_60") (pintype "bidirectional"))
    )
    (net (code "115") (name "unconnected-(IC1A-PE10-Pad63)") (class "Default")
      (node (ref "IC1") (pin "63") (pinfunction "PE10_63") (pintype "bidirectional"))
    )
    (net (code "116") (name "unconnected-(IC1A-PE11-Pad64)") (class "Default")
      (node (ref "IC1") (pin "64") (pinfunction "PE11_64") (pintype "bidirectional"))
    )
    (net (code "117") (name "unconnected-(IC1A-PE12-Pad65)") (class "Default")
      (node (ref "IC1") (pin "65") (pinfunction "PE12_65") (pintype "bidirectional"))
    )
    (net (code "118") (name "unconnected-(IC1A-PE13-Pad66)") (class "Default")
      (node (ref "IC1") (pin "66") (pinfunction "PE13_66") (pintype "bidirectional"))
    )
    (net (code "119") (name "unconnected-(IC1A-PE14-Pad67)") (class "Default")
      (node (ref "IC1") (pin "67") (pinfunction "PE14_67") (pintype "bidirectional"))
    )
    (net (code "120") (name "unconnected-(IC1A-PE15-Pad68)") (class "Default")
      (node (ref "IC1") (pin "68") (pinfunction "PE15_68") (pintype "bidirectional"))
    )
    (net (code "121") (name "unconnected-(IC1A-PF0-Pad10)") (class "Default")
      (node (ref "IC1") (pin "10") (pinfunction "PF0_10") (pintype "bidirectional"))
    )
    (net (code "122") (name "unconnected-(IC1A-PF1-Pad11)") (class "Default")
      (node (ref "IC1") (pin "11") (pinfunction "PF1_11") (pintype "bidirectional"))
    )
    (net (code "123") (name "unconnected-(IC1A-PF2-Pad12)") (class "Default")
      (node (ref "IC1") (pin "12") (pinfunction "PF2_12") (pintype "bidirectional"))
    )
    (net (code "124") (name "unconnected-(IC1A-PF3-Pad13)") (class "Default")
      (node (ref "IC1") (pin "13") (pinfunction "PF3_13") (pintype "bidirectional"))
    )
    (net (code "125") (name "unconnected-(IC1A-PF4-Pad14)") (class "Default")
      (node (ref "IC1") (pin "14") (pinfunction "PF4_14") (pintype "bidirectional"))
    )
    (net (code "126") (name "unconnected-(IC1A-PF5-Pad15)") (class "Default")
      (node (ref "IC1") (pin "15") (pinfunction "PF5_15") (pintype "bidirectional"))
    )
    (net (code "127") (name "unconnected-(IC1A-PF8-Pad20)") (class "Default")
      (node (ref "IC1") (pin "20") (pinfunction "PF8_20") (pintype "bidirectional"))
    )
    (net (code "128") (name "unconnected-(IC1A-PF11-Pad49)") (class "Default")
      (node (ref "IC1") (pin "49") (pinfunction "PF11_49") (pintype "bidirectional"))
    )
    (net (code "129") (name "unconnected-(IC1A-PF12-Pad50)") (class "Default")
      (node (ref "IC1") (pin "50") (pinfunction "PF12_50") (pintype "bidirectional"))
    )
    (net (code "130") (name "unconnected-(IC1A-PF13-Pad53)") (class "Default")
      (node (ref "IC1") (pin "53") (pinfunction "PF13_53") (pintype "bidirectional"))
    )
    (net (code "131") (name "unconnected-(IC1A-PF14-Pad54)") (class "Default")
      (node (ref "IC1") (pin "54") (pinfunction "PF14_54") (pintype "bidirectional"))
    )
    (net (code "132") (name "unconnected-(IC1A-PF15-Pad55)") (class "Default")
      (node (ref "IC1") (pin "55") (pinfunction "PF15_55") (pintype "bidirectional"))
    )
    (net (code "133") (name "unconnected-(IC1A-PG0-Pad56)") (class "Default")
      (node (ref "IC1") (pin "56") (pinfunction "PG0_56") (pintype "bidirectional"))
    )
    (net (code "134") (name "unconnected-(IC1A-PG1-Pad57)") (class "Default")
      (node (ref "IC1") (pin "57") (pinfunction "PG1_57") (pintype "bidirectional"))
    )
    (net (code "135") (name "unconnected-(IC1A-PG2-Pad87)") (class "Default")
      (node (ref "IC1") (pin "87") (pinfunction "PG2_87") (pintype "bidirectional"))
    )
    (net (code "136") (name "unconnected-(IC1A-PG3-Pad88)") (class "Default")
      (node (ref "IC1") (pin "88") (pinfunction "PG3_88") (pintype "bidirectional"))
    )
    (net (code "137") (name "unconnected-(IC1A-PG4-Pad89)") (class "Default")
      (node (ref "IC1") (pin "89") (pinfunction "PG4_89") (pintype "bidirectional"))
    )
    (net (code "138") (name "unconnected-(IC1A-PG5-Pad90)") (class "Default")
      (node (ref "IC1") (pin "90") (pinfunction "PG5_90") (pintype "bidirectional"))
    )
    (net (code "139") (name "unconnected-(IC1A-PG6-Pad91)") (class "Default")
      (node (ref "IC1") (pin "91") (pinfunction "PG6_91") (pintype "bidirectional"))
    )
    (net (code "140") (name "unconnected-(IC1A-PG7-Pad92)") (class "Default")
      (node (ref "IC1") (pin "92") (pinfunction "PG7_92") (pintype "bidirectional"))
    )
    (net (code "141") (name "unconnected-(IC1A-PG8-Pad93)") (class "Default")
      (node (ref "IC1") (pin "93") (pinfunction "PG8_93") (pintype "bidirectional"))
    )
    (net (code "142") (name "unconnected-(IC1A-PG9-Pad124)") (class "Default")
      (node (ref "IC1") (pin "124") (pinfunction "PG9_124") (pintype "bidirectional"))
    )
    (net (code "143") (name "unconnected-(IC1A-PG10-Pad125)") (class "Default")
      (node (ref "IC1") (pin "125") (pinfunction "PG10_125") (pintype "bidirectional"))
    )
    (net (code "144") (name "unconnected-(IC1A-PG11-Pad126)") (class "Default")
      (node (ref "IC1") (pin "126") (pinfunction "PG11_126") (pintype "bidirectional"))
    )
    (net (code "145") (name "unconnected-(IC1A-PG12-Pad127)") (class "Default")
      (node (ref "IC1") (pin "127") (pinfunction "PG12_127") (pintype "bidirectional"))
    )
    (net (code "146") (name "unconnected-(RT9013-1-NC-Pad4)") (class "Default")
      (node (ref "RT9013-1") (pin "4") (pinfunction "NC_4") (pintype "bidirectional"))
    )
    (net (code "147") (name "unconnected-(SW-1-B-PadP$1)") (class "Default")
      (node (ref "SW-1") (pin "P$1") (pinfunction "B_P$1") (pintype "bidirectional"))
    )
    (net (code "148") (name "unconnected-(SW3P-1-COM-Pad3)") (class "Default")
      (node (ref "SW3P-1") (pin "3") (pinfunction "COM_3") (pintype "bidirectional"))
    )
    (net (code "149") (name "unconnected-(SW3P-2-COM-Pad3)") (class "Default")
      (node (ref "SW3P-2") (pin "3") (pinfunction "COM_3") (pintype "bidirectional"))
    )
    (net (code "150") (name "unconnected-(USB2-ID-Pad4)") (class "Default")
      (node (ref "USB2") (pin "4") (pinfunction "ID_4") (pintype "bidirectional"))
    )
    (net (code "151") (name "unconnected-(Y1-1-Pad4)") (class "Default")
      (node (ref "Y1") (pin "4") (pinfunction "1_4") (pintype "bidirectional"))
    )
    (net (code "152") (name "unconnected-(Y1-3-Pad2)") (class "Default")
      (node (ref "Y1") (pin "2") (pinfunction "3_2") (pintype "bidirectional"))
    )
  )
)
